# BMSBoard.net
KiCad netlist of a schematic drawn in EAGLE
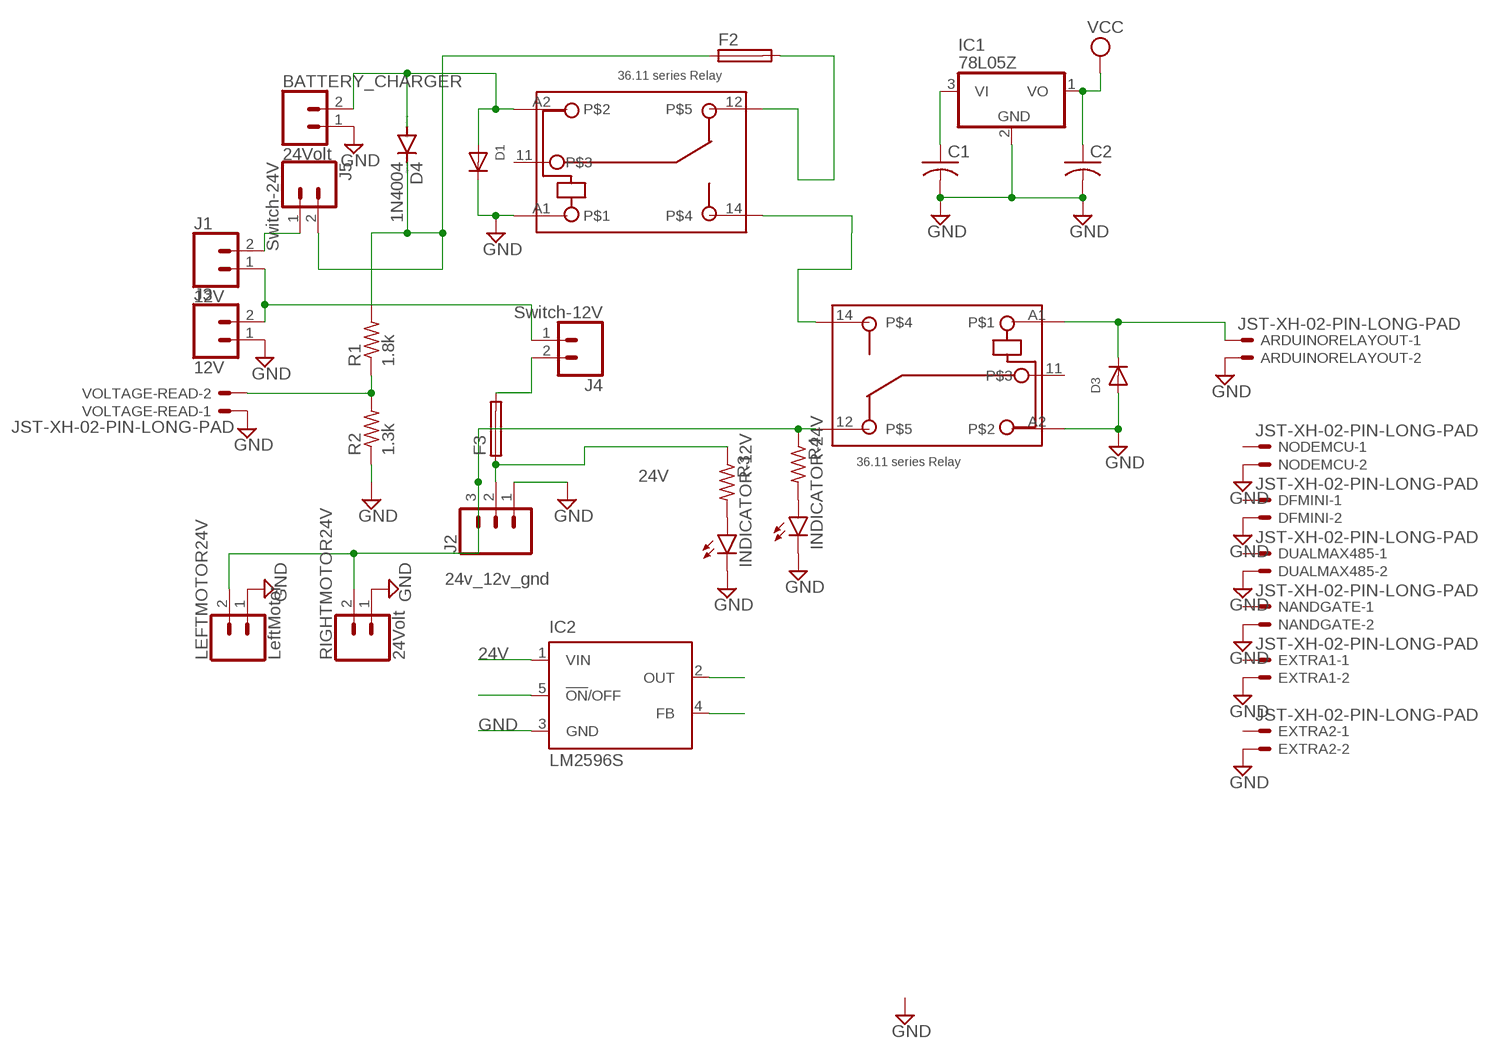
[diagram p0: schematic, sheet 1]

(export (version "E")
  (design (tool "Eeschema 10.0.6"))
  (components
    (comp (ref "ARDUINORELAYOUT")
      (value "JST-XH-02-PIN-LONG-PAD")
      (footprint "eagle-import:JST-XH-02-PACKAGE-LONG-PAD")
      (libsource (lib "eagle-import") (part "JST-XH-02-PIN-LONG-PAD"))
    )
    (comp (ref "BATTERY_CHARGER")
      (value "24Volt")
      (footprint "eagle-import:SCREWTERMINAL-3.5MM-2")
      (libsource (lib "eagle-import") (part "CONN_023.5MM"))
    )
    (comp (ref "BMSRELAY")
      (value "36.11")
      (footprint "eagle-import:36.11")
      (libsource (lib "eagle-import") (part "36.11"))
    )
    (comp (ref "C1")
      (value "C-US025-024X044")
      (footprint "eagle-import:C025-024X044")
      (libsource (lib "eagle-import") (part "C-US025-024X044"))
    )
    (comp (ref "C2")
      (value "C-US025-024X044")
      (footprint "eagle-import:C025-024X044")
      (libsource (lib "eagle-import") (part "C-US025-024X044"))
    )
    (comp (ref "CHARGERRELAY")
      (value "36.11")
      (footprint "eagle-import:36.11")
      (libsource (lib "eagle-import") (part "36.11"))
    )
    (comp (ref "D1")
      (value "DIODEDO-1N4148")
      (footprint "eagle-import:DO-1N4148")
      (libsource (lib "eagle-import") (part "DIODEDO-1N4148"))
    )
    (comp (ref "D3")
      (value "DIODEDO-1N4148")
      (footprint "eagle-import:DO-1N4148")
      (libsource (lib "eagle-import") (part "DIODEDO-1N4148"))
    )
    (comp (ref "D4")
      (value "1N4004")
      (footprint "eagle-import:DO41-10")
      (libsource (lib "eagle-import") (part "1N4004"))
    )
    (comp (ref "DFMINI")
      (value "JST-XH-02-PIN-LONG-PAD")
      (footprint "eagle-import:JST-XH-02-PACKAGE-LONG-PAD")
      (libsource (lib "eagle-import") (part "JST-XH-02-PIN-LONG-PAD"))
    )
    (comp (ref "DUALMAX485")
      (value "JST-XH-02-PIN-LONG-PAD")
      (footprint "eagle-import:JST-XH-02-PACKAGE-LONG-PAD")
      (libsource (lib "eagle-import") (part "JST-XH-02-PIN-LONG-PAD"))
    )
    (comp (ref "EXTRA1")
      (value "JST-XH-02-PIN-LONG-PAD")
      (footprint "eagle-import:JST-XH-02-PACKAGE-LONG-PAD")
      (libsource (lib "eagle-import") (part "JST-XH-02-PIN-LONG-PAD"))
    )
    (comp (ref "EXTRA2")
      (value "JST-XH-02-PIN-LONG-PAD")
      (footprint "eagle-import:JST-XH-02-PACKAGE-LONG-PAD")
      (libsource (lib "eagle-import") (part "JST-XH-02-PIN-LONG-PAD"))
    )
    (comp (ref "F2")
      (value "19560")
      (footprint "eagle-import:19560")
      (fields (field (name "MPN") "56000001009"))
      (libsource (lib "eagle-import") (part "19560"))
    )
    (comp (ref "F3")
      (value "19560")
      (footprint "eagle-import:19560")
      (fields (field (name "MPN") "56000001009"))
      (libsource (lib "eagle-import") (part "19560"))
    )
    (comp (ref "IC1")
      (value "78L05Z")
      (footprint "eagle-import:TO92")
      (libsource (lib "eagle-import") (part "78ZL05"))
    )
    (comp (ref "IC2")
      (value "LM2596S")
      (footprint "eagle-import:TO263-5")
      (fields (field (name "MF") "NATIONAL SEMICONDUCTOR") (field (name "MPN") "LM2596S-ADJ/NOPB"))
      (libsource (lib "eagle-import") (part "LM2596S"))
    )
    (comp (ref "INDICATOR-12V")
      (value "LED")
      (footprint "eagle-import:SMARTLED-TTW")
      (libsource (lib "eagle-import") (part "LED"))
    )
    (comp (ref "INDICATOR-24V")
      (value "LED")
      (footprint "eagle-import:SMARTLED-TTW")
      (libsource (lib "eagle-import") (part "LED"))
    )
    (comp (ref "J1")
      (value "12V")
      (footprint "eagle-import:SCREWTERMINAL-3.5MM-2")
      (libsource (lib "eagle-import") (part "CONN_023.5MM"))
    )
    (comp (ref "J2")
      (value "24v_12v_gnd")
      (footprint "eagle-import:SCREWTERMINAL-5MM-3")
      (libsource (lib "eagle-import") (part "CONN_03-SCREW-5MM"))
    )
    (comp (ref "J3")
      (value "12V")
      (footprint "eagle-import:SCREWTERMINAL-3.5MM-2")
      (libsource (lib "eagle-import") (part "CONN_023.5MM"))
    )
    (comp (ref "J4")
      (value "Switch-12V")
      (footprint "eagle-import:SCREWTERMINAL-3.5MM-2")
      (libsource (lib "eagle-import") (part "CONN_023.5MM"))
    )
    (comp (ref "J5")
      (value "Switch-24V")
      (footprint "eagle-import:SCREWTERMINAL-3.5MM-2")
      (libsource (lib "eagle-import") (part "CONN_023.5MM"))
    )
    (comp (ref "LEFTMOTOR24V")
      (value "LeftMotor")
      (footprint "eagle-import:SCREWTERMINAL-3.5MM-2")
      (libsource (lib "eagle-import") (part "CONN_023.5MM"))
    )
    (comp (ref "NANDGATE")
      (value "JST-XH-02-PIN-LONG-PAD")
      (footprint "eagle-import:JST-XH-02-PACKAGE-LONG-PAD")
      (libsource (lib "eagle-import") (part "JST-XH-02-PIN-LONG-PAD"))
    )
    (comp (ref "NODEMCU")
      (value "JST-XH-02-PIN-LONG-PAD")
      (footprint "eagle-import:JST-XH-02-PACKAGE-LONG-PAD")
      (libsource (lib "eagle-import") (part "JST-XH-02-PIN-LONG-PAD"))
    )
    (comp (ref "R1")
      (value "1.8k")
      (footprint "eagle-import:0204_7")
      (libsource (lib "eagle-import") (part "R-US_0204/7"))
    )
    (comp (ref "R2")
      (value "1.3k")
      (footprint "eagle-import:0204_7")
      (libsource (lib "eagle-import") (part "R-US_0204/7"))
    )
    (comp (ref "R3")
      (value "R-US_0204/2V")
      (footprint "eagle-import:0204V")
      (libsource (lib "eagle-import") (part "R-US_0204/2V"))
    )
    (comp (ref "R4")
      (value "R-US_0204/2V")
      (footprint "eagle-import:0204V")
      (libsource (lib "eagle-import") (part "R-US_0204/2V"))
    )
    (comp (ref "RIGHTMOTOR24V")
      (value "24Volt")
      (footprint "eagle-import:SCREWTERMINAL-3.5MM-2")
      (libsource (lib "eagle-import") (part "CONN_023.5MM"))
    )
    (comp (ref "VOLTAGE-READ")
      (value "JST-XH-02-PIN-LONG-PAD")
      (footprint "eagle-import:JST-XH-02-PACKAGE-LONG-PAD")
      (libsource (lib "eagle-import") (part "JST-XH-02-PIN-LONG-PAD"))
    )
  )
  (nets
    (net (code "1") (name "/24V") (class "Default")
      (node (ref "F3") (pin "1") (pinfunction "1_1") (pintype "passive"))
      (node (ref "IC2") (pin "1") (pinfunction "VIN_1") (pintype "input"))
      (node (ref "J2") (pin "2") (pinfunction "2_2") (pintype "passive"))
      (node (ref "R3") (pin "1") (pinfunction "1_1") (pintype "passive"))
    )
    (net (code "2") (name "GND") (class "Default")
      (node (ref "ARDUINORELAYOUT") (pin "2") (pinfunction "S_2") (pintype "passive"))
      (node (ref "BATTERY_CHARGER") (pin "1") (pinfunction "1_1") (pintype "passive"))
      (node (ref "BMSRELAY") (pin "A2") (pinfunction "P$2_A2") (pintype "passive"))
      (node (ref "C1") (pin "2") (pinfunction "2_2") (pintype "passive"))
      (node (ref "C2") (pin "2") (pinfunction "2_2") (pintype "passive"))
      (node (ref "CHARGERRELAY") (pin "A1") (pinfunction "P$1_A1") (pintype "passive"))
      (node (ref "D1") (pin "C") (pinfunction "C_C") (pintype "passive"))
      (node (ref "D3") (pin "A") (pinfunction "A_A") (pintype "passive"))
      (node (ref "DFMINI") (pin "2") (pinfunction "S_2") (pintype "passive"))
      (node (ref "DUALMAX485") (pin "2") (pinfunction "S_2") (pintype "passive"))
      (node (ref "EXTRA1") (pin "2") (pinfunction "S_2") (pintype "passive"))
      (node (ref "EXTRA2") (pin "2") (pinfunction "S_2") (pintype "passive"))
      (node (ref "IC1") (pin "2") (pinfunction "GND_2") (pintype "passive"))
      (node (ref "IC2") (pin "3") (pinfunction "GND_3") (pintype "power_in"))
      (node (ref "INDICATOR-12V") (pin "C@1") (pinfunction "C_C@1") (pintype "passive"))
      (node (ref "INDICATOR-24V") (pin "C@1") (pinfunction "C_C@1") (pintype "passive"))
      (node (ref "J2") (pin "1") (pinfunction "1_1") (pintype "passive"))
      (node (ref "J3") (pin "1") (pinfunction "1_1") (pintype "passive"))
      (node (ref "LEFTMOTOR24V") (pin "1") (pinfunction "1_1") (pintype "passive"))
      (node (ref "NANDGATE") (pin "2") (pinfunction "S_2") (pintype "passive"))
      (node (ref "NODEMCU") (pin "2") (pinfunction "S_2") (pintype "passive"))
      (node (ref "R2") (pin "1") (pinfunction "1_1") (pintype "passive"))
      (node (ref "RIGHTMOTOR24V") (pin "1") (pinfunction "1_1") (pintype "passive"))
      (node (ref "VOLTAGE-READ") (pin "1") (pinfunction "S_1") (pintype "passive"))
    )
    (net (code "3") (name "Net-(ARDUINORELAYOUTA-S)") (class "Default")
      (node (ref "ARDUINORELAYOUT") (pin "1") (pinfunction "S_1") (pintype "passive"))
      (node (ref "BMSRELAY") (pin "A1") (pinfunction "P$1_A1") (pintype "passive"))
      (node (ref "D3") (pin "C") (pinfunction "C_C") (pintype "passive"))
    )
    (net (code "4") (name "Net-(BMSRELAY-P$4)") (class "Default")
      (node (ref "BMSRELAY") (pin "14") (pinfunction "P$4_14") (pintype "passive"))
      (node (ref "CHARGERRELAY") (pin "14") (pinfunction "P$4_14") (pintype "passive"))
    )
    (net (code "5") (name "Net-(BMSRELAY-P$5)") (class "Default")
      (node (ref "BMSRELAY") (pin "12") (pinfunction "P$5_12") (pintype "passive"))
      (node (ref "J2") (pin "3") (pinfunction "3_3") (pintype "passive"))
      (node (ref "LEFTMOTOR24V") (pin "2") (pinfunction "2_2") (pintype "passive"))
      (node (ref "R4") (pin "1") (pinfunction "1_1") (pintype "passive"))
      (node (ref "RIGHTMOTOR24V") (pin "2") (pinfunction "2_2") (pintype "passive"))
    )
    (net (code "6") (name "Net-(CHARGERRELAY-P$2)") (class "Default")
      (node (ref "BATTERY_CHARGER") (pin "2") (pinfunction "2_2") (pintype "passive"))
      (node (ref "CHARGERRELAY") (pin "A2") (pinfunction "P$2_A2") (pintype "passive"))
      (node (ref "D1") (pin "A") (pinfunction "A_A") (pintype "passive"))
      (node (ref "D4") (pin "A") (pinfunction "A_A") (pintype "passive"))
    )
    (net (code "7") (name "Net-(CHARGERRELAY-P$5)") (class "Default")
      (node (ref "CHARGERRELAY") (pin "12") (pinfunction "P$5_12") (pintype "passive"))
      (node (ref "F2") (pin "2") (pinfunction "2_2") (pintype "passive"))
    )
    (net (code "8") (name "Net-(D4-PadC)") (class "Default")
      (node (ref "D4") (pin "C") (pinfunction "C_C") (pintype "passive"))
      (node (ref "F2") (pin "1") (pinfunction "1_1") (pintype "passive"))
      (node (ref "J5") (pin "2") (pinfunction "2_2") (pintype "passive"))
      (node (ref "R1") (pin "2") (pinfunction "2_2") (pintype "passive"))
    )
    (net (code "9") (name "Net-(F3-Pad2)") (class "Default")
      (node (ref "F3") (pin "2") (pinfunction "2_2") (pintype "passive"))
      (node (ref "J4") (pin "2") (pinfunction "2_2") (pintype "passive"))
    )
    (net (code "10") (name "Net-(IC1-VI)") (class "Default")
      (node (ref "C1") (pin "1") (pinfunction "1_1") (pintype "passive"))
      (node (ref "IC1") (pin "3") (pinfunction "VI_3") (pintype "input"))
    )
    (net (code "11") (name "Net-(INDICATOR-12V-A)") (class "Default")
      (node (ref "INDICATOR-12V") (pin "A@1") (pinfunction "A_A@1") (pintype "passive"))
      (node (ref "R3") (pin "2") (pinfunction "2_2") (pintype "passive"))
    )
    (net (code "12") (name "Net-(INDICATOR-24V-A)") (class "Default")
      (node (ref "INDICATOR-24V") (pin "A@1") (pinfunction "A_A@1") (pintype "passive"))
      (node (ref "R4") (pin "2") (pinfunction "2_2") (pintype "passive"))
    )
    (net (code "13") (name "Net-(J1-Pad1)") (class "Default")
      (node (ref "J1") (pin "1") (pinfunction "1_1") (pintype "passive"))
      (node (ref "J3") (pin "2") (pinfunction "2_2") (pintype "passive"))
      (node (ref "J4") (pin "1") (pinfunction "1_1") (pintype "passive"))
    )
    (net (code "14") (name "Net-(J1-Pad2)") (class "Default")
      (node (ref "J1") (pin "2") (pinfunction "2_2") (pintype "passive"))
      (node (ref "J5") (pin "1") (pinfunction "1_1") (pintype "passive"))
    )
    (net (code "15") (name "Net-(VOLTAGE-READB-S)") (class "Default")
      (node (ref "R1") (pin "1") (pinfunction "1_1") (pintype "passive"))
      (node (ref "R2") (pin "2") (pinfunction "2_2") (pintype "passive"))
      (node (ref "VOLTAGE-READ") (pin "2") (pinfunction "S_2") (pintype "passive"))
    )
    (net (code "16") (name "VCC") (class "Default")
      (node (ref "C2") (pin "1") (pinfunction "1_1") (pintype "passive"))
      (node (ref "IC1") (pin "1") (pinfunction "VO_1") (pintype "passive"))
    )
    (net (code "17") (name "unconnected-(BMSRELAY-P$3-Pad11)") (class "Default")
      (node (ref "BMSRELAY") (pin "11") (pinfunction "P$3_11") (pintype "passive"))
    )
    (net (code "18") (name "unconnected-(CHARGERRELAY-P$3-Pad11)") (class "Default")
      (node (ref "CHARGERRELAY") (pin "11") (pinfunction "P$3_11") (pintype "passive"))
    )
    (net (code "19") (name "unconnected-(DFMINIA-S-Pad1)") (class "Default")
      (node (ref "DFMINI") (pin "1") (pinfunction "S_1") (pintype "passive"))
    )
    (net (code "20") (name "unconnected-(DUALMAX485A-S-Pad1)") (class "Default")
      (node (ref "DUALMAX485") (pin "1") (pinfunction "S_1") (pintype "passive"))
    )
    (net (code "21") (name "unconnected-(EXTRA1A-S-Pad1)") (class "Default")
      (node (ref "EXTRA1") (pin "1") (pinfunction "S_1") (pintype "passive"))
    )
    (net (code "22") (name "unconnected-(EXTRA2A-S-Pad1)") (class "Default")
      (node (ref "EXTRA2") (pin "1") (pinfunction "S_1") (pintype "passive"))
    )
    (net (code "23") (name "unconnected-(IC2-FB-Pad4)") (class "Default")
      (node (ref "IC2") (pin "4") (pinfunction "FB_4") (pintype "input"))
    )
    (net (code "24") (name "unconnected-(IC2-OUT-Pad2)") (class "Default")
      (node (ref "IC2") (pin "2") (pinfunction "OUT_2") (pintype "output"))
    )
    (net (code "25") (name "unconnected-(IC2-~{ON}{slash}OFF-Pad5)") (class "Default")
      (node (ref "IC2") (pin "5") (pinfunction "~{ON}/OFF_5") (pintype "input"))
    )
    (net (code "26") (name "unconnected-(NANDGATEA-S-Pad1)") (class "Default")
      (node (ref "NANDGATE") (pin "1") (pinfunction "S_1") (pintype "passive"))
    )
    (net (code "27") (name "unconnected-(NODEMCUA-S-Pad1)") (class "Default")
      (node (ref "NODEMCU") (pin "1") (pinfunction "S_1") (pintype "passive"))
    )
  )
)
